# LKS32MC038Y6P8B_BP85226DF_LKSP1D5007D_V1.net
KiCad netlist of a schematic drawn in Altium Designer
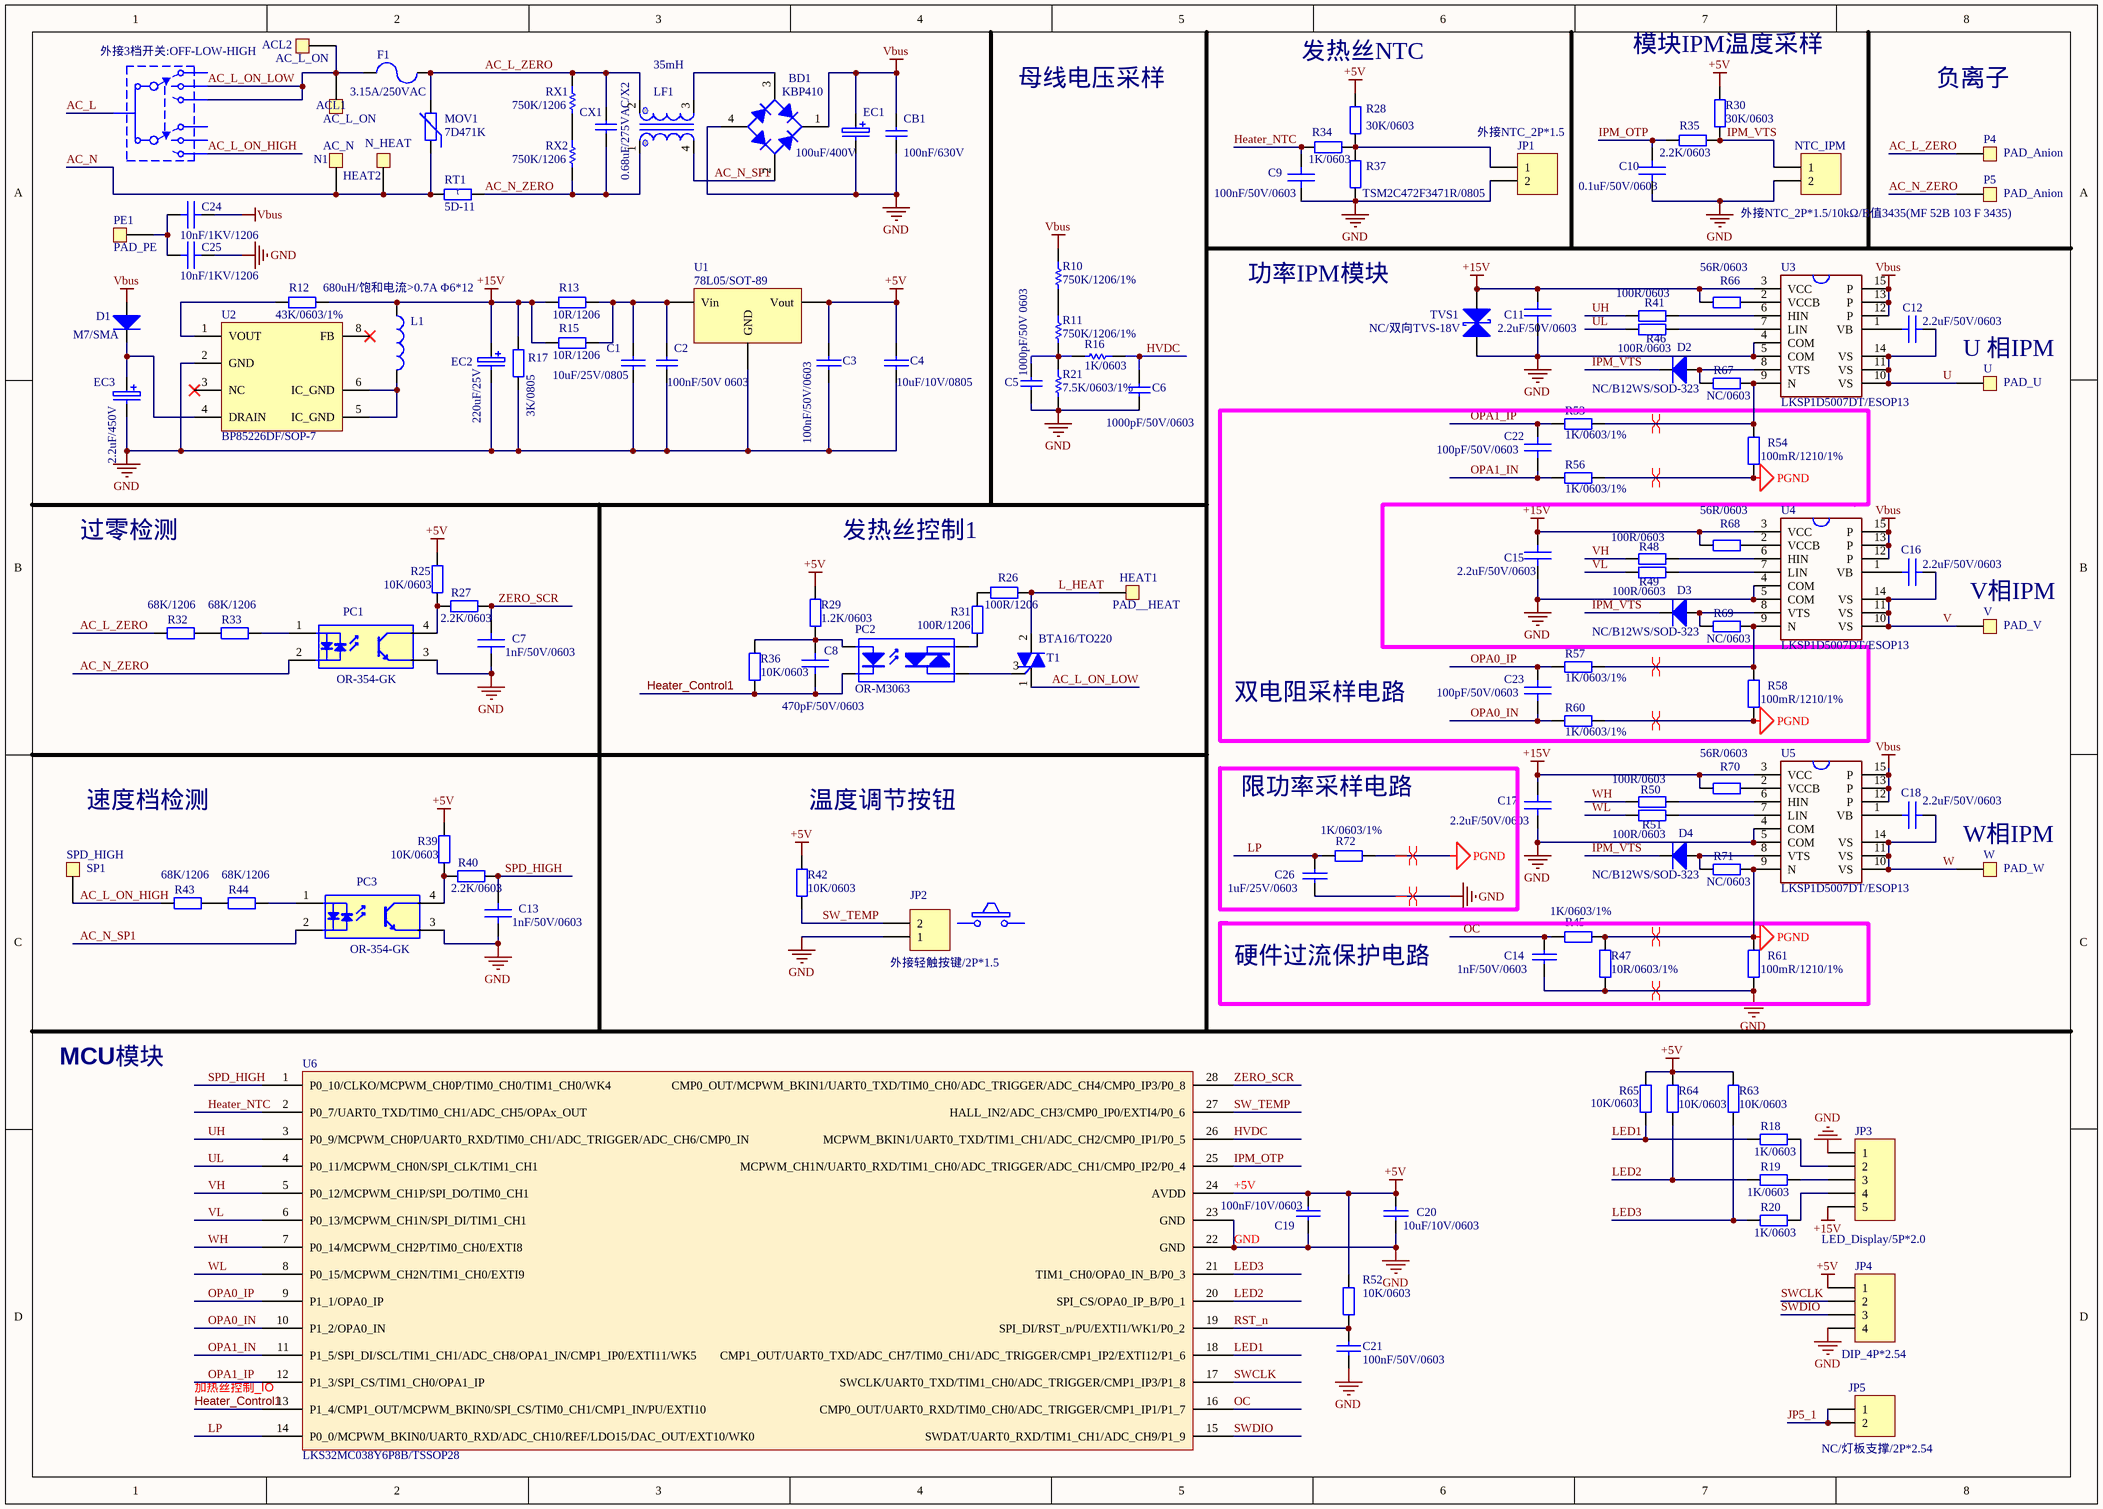
[diagram p0: LKS32MC038Y6P8B+BP85226DF+LKSP1D5007D_V1.0_SCH_20230419.SchDoc]

(export (version "E")
  (design (tool "Eeschema 10.0.6"))
  (components
    (comp (ref "ACL1") (value "AC_L_ON") (footprint "22AWG") (libsource (lib "") (part "Header-1-PE_3")))
    (comp (ref "ACL2")
      (value "AC_L_ON")
      (footprint "22AWG")
      (libsource (lib "Sch-LIB-chen") (part "Header-1-PE"))
    )
    (comp (ref "BD1") (value "KBP410") (footprint "KBP210") (libsource (lib "Sch-LIB-chen") (part "BD")))
    (comp (ref "C1")
      (value "10uF/25V/0805")
      (footprint "C0805")
      (description "Capacitor")
      (libsource (lib "*") (part "C"))
    )
    (comp (ref "C2")
      (value "100nF/50V 0603")
      (footprint "C0603")
      (libsource (lib "Sch-LIB-chen") (part "C-0603"))
    )
    (comp (ref "C3")
      (value "100nF/50V/0603")
      (footprint "C0603")
      (description "Capacitor")
      (libsource (lib "*") (part "C"))
    )
    (comp (ref "C4")
      (value "10uF/10V/0805")
      (footprint "C0805")
      (description "Capacitor")
      (libsource (lib "*") (part "C"))
    )
    (comp (ref "C5")
      (value "1000pF/50V 0603")
      (footprint "C0603")
      (libsource (lib "Sch-LIB-chen") (part "C-0603"))
    )
    (comp (ref "C6")
      (value "1000pF/50V/0603")
      (footprint "C0603")
      (libsource (lib "Sch-LIB-chen") (part "C-0603"))
    )
    (comp (ref "C7")
      (value "1nF/50V/0603")
      (footprint "C0603")
      (libsource (lib "TEK_CHIP-sch") (part "C-0603-104K50-X7R"))
    )
    (comp (ref "C8")
      (value "470pF/50V/0603")
      (footprint "C0603")
      (description "C-0603")
      (libsource (lib "TEK_CHIP-sch") (part "C-0603-471K50-X7R"))
    )
    (comp (ref "C9")
      (value "100nF/50V/0603")
      (footprint "C0603")
      (libsource (lib "TEK_CHIP-sch") (part "C-0603-104K50-X7R"))
    )
    (comp (ref "C10")
      (value "0.1uF/50V/0603")
      (footprint "C0603")
      (libsource (lib "TEK_CHIP-sch") (part "C-0603-104K50-X7R"))
    )
    (comp (ref "C11")
      (value "2.2uF/50V/0603")
      (footprint "C1206")
      (description "0805")
      (libsource (lib "TEK_CHIP-sch") (part "C-0805-475K50-X7R"))
    )
    (comp (ref "C12")
      (value "2.2uF/50V/0603")
      (footprint "C0805")
      (description "C-0805")
      (libsource (lib "SCH-Tineco") (part "C-0805-225K50-X7R"))
    )
    (comp (ref "C13")
      (value "1nF/50V/0603")
      (footprint "C0603")
      (libsource (lib "TEK_CHIP-sch") (part "C-0603-104K50-X7R"))
    )
    (comp (ref "C14")
      (value "1nF/50V/0603")
      (footprint "C0603")
      (description "Capacitor")
      (libsource (lib "*") (part "C"))
    )
    (comp (ref "C15")
      (value "2.2uF/50V/0603")
      (footprint "C1206")
      (description "0805")
      (libsource (lib "TEK_CHIP-sch") (part "C-0805-475K50-X7R"))
    )
    (comp (ref "C16")
      (value "2.2uF/50V/0603")
      (footprint "C0805")
      (description "C-0805")
      (libsource (lib "SCH-Tineco") (part "C-0805-225K50-X7R"))
    )
    (comp (ref "C17")
      (value "2.2uF/50V/0603")
      (footprint "C1206")
      (description "0805")
      (libsource (lib "TEK_CHIP-sch") (part "C-0805-475K50-X7R"))
    )
    (comp (ref "C18")
      (value "2.2uF/50V/0603")
      (footprint "C0805")
      (description "C-0805")
      (libsource (lib "SCH-Tineco") (part "C-0805-225K50-X7R"))
    )
    (comp (ref "C19")
      (value "100nF/10V/0603")
      (footprint "C0603")
      (description "Capacitor")
      (libsource (lib "*") (part "C"))
    )
    (comp (ref "C20")
      (value "10uF/10V/0603")
      (footprint "C0603")
      (description "Capacitor")
      (libsource (lib "*") (part "C"))
    )
    (comp (ref "C21")
      (value "100nF/50V/0603")
      (footprint "C0603")
      (description "Capacitor")
      (libsource (lib "*") (part "C"))
    )
    (comp (ref "C22")
      (value "100pF/50V/0603")
      (footprint "C0603")
      (description "0805")
      (libsource (lib "TEK_CHIP-sch") (part "C-0805-475K50-X7R"))
    )
    (comp (ref "C23")
      (value "100pF/50V/0603")
      (footprint "C0603")
      (description "0805")
      (libsource (lib "TEK_CHIP-sch") (part "C-0805-475K50-X7R"))
    )
    (comp (ref "C24")
      (value "10nF/1KV/1206")
      (footprint "C1206")
      (description "0805")
      (libsource (lib "TEK_CHIP-sch") (part "C-0805-475K50-X7R"))
    )
    (comp (ref "C25")
      (value "10nF/1KV/1206")
      (footprint "C1206")
      (description "0805")
      (libsource (lib "TEK_CHIP-sch") (part "C-0805-475K50-X7R"))
    )
    (comp (ref "C26")
      (value "1uF/25V/0603")
      (footprint "C0603")
      (description "Capacitor")
      (libsource (lib "*") (part "C"))
    )
    (comp (ref "CB1")
      (value "100nF/630V")
      (footprint "CY2-7.5")
      (libsource (lib "Sch-LIB-chen") (part "CBB-12*6-P10"))
    )
    (comp (ref "CX1")
      (value "0.68uF/275VAC/X2")
      (footprint "0.68uF_X2_L12.8*W7.8*H13.6")
      (libsource (lib "Sch-LIB-chen") (part "CX-18*8.5-P15"))
    )
    (comp (ref "D1")
      (value "M7/SMA")
      (footprint "SMD-(DO-214AC/SMA)(H)")
      (description "SOD-123")
      (libsource (lib "TEK_CHIP-sch") (part "D-1N4148W"))
    )
    (comp (ref "D2")
      (value "NC/B12WS/SOD-323")
      (footprint "SOD-323")
      (description "SOD-123")
      (libsource (lib "TEK_CHIP-sch") (part "D-1N4148W"))
    )
    (comp (ref "D3")
      (value "NC/B12WS/SOD-323")
      (footprint "SOD-323")
      (description "SOD-123")
      (libsource (lib "TEK_CHIP-sch") (part "D-1N4148W"))
    )
    (comp (ref "D4")
      (value "NC/B12WS/SOD-323")
      (footprint "SOD-323")
      (description "SOD-123")
      (libsource (lib "TEK_CHIP-sch") (part "D-1N4148W"))
    )
    (comp (ref "EC1") (value "100uF/400V") (footprint "E18*32W") (libsource (lib "Sch-LIB-chen") (part "CD")))
    (comp (ref "EC2") (value "220uF/25V") (footprint "E6.3*7") (libsource (lib "Sch-LIB-chen") (part "CD-8")))
    (comp (ref "EC3")
      (value "2.2uF/450V")
      (footprint "E6.3*7")
      (libsource (lib "Sch-LIB-chen") (part "CD-8"))
    )
    (comp (ref "F1")
      (value "3.15A/250VAC")
      (footprint "FUSE-6528")
      (libsource (lib "Sch-LIB-chen") (part "FUSE-3.6*10"))
    )
    (comp (ref "HEAT1") (value "PAD__HEAT") (footprint "22AWG") (libsource (lib "") (part "Header-1-PE_1")))
    (comp (ref "HEAT2") (value "N_HEAT") (footprint "22AWG") (libsource (lib "") (part "Header-1-PE_2")))
    (comp (ref "JP1")
      (value "外接NTC_2P*1.5")
      (footprint "XH25-2ADW")
      (description "Header, 2-Pin")
      (fields (field (name "PUBLISHER") "Altium Limited"))
      (libsource (lib "Miscellaneous Connectors") (part "Header 2"))
    )
    (comp (ref "JP2")
      (value "外接轻触按键/2P*1.5")
      (footprint "XH25-2ADW")
      (description "Header, 2-Pin")
      (fields (field (name "PUBLISHER") "Altium Limited"))
      (libsource (lib "") (part "Header 2_1"))
    )
    (comp (ref "JP3")
      (value "LED_Display/5P*2.0")
      (footprint "PH20-5AW")
      (description "Header, 5-Pin")
      (fields (field (name "PUBLISHER") "Altium Limited"))
      (libsource (lib "Miscellaneous Connectors") (part "Header 5"))
    )
    (comp (ref "JP4")
      (value "DIP_4P*2.54")
      (footprint "JP4_P2.54")
      (description "Header, 4-Pin")
      (fields (field (name "PUBLISHER") "Altium Limited"))
      (libsource (lib "Miscellaneous Connectors") (part "Header 4"))
    )
    (comp (ref "JP5")
      (value "NC/灯板支撑/2P*2.54")
      (footprint "HDR1X2")
      (description "Header, 2-Pin")
      (fields (field (name "PUBLISHER") "Altium Limited"))
      (libsource (lib "Miscellaneous Connectors") (part "Header 2"))
    )
    (comp (ref "L1")
      (value "680uH/饱和电流>0.7A Φ6*12")
      (footprint "L3.0")
      (libsource (lib "Sch-LIB-chen") (part "L-Φ10"))
    )
    (comp (ref "LF1") (value "35mH") (footprint "L17MM") (libsource (lib "Sch-LIB-chen") (part "L--CM")))
    (comp (ref "MOV1")
      (value "7D471K")
      (footprint "07D561")
      (description "压敏")
      (libsource (lib "Sch-LIB-chen") (part "RV-10D"))
    )
    (comp (ref "N1") (value "AC_N") (footprint "22AWG") (libsource (lib "") (part "Header-1-PE_2")))
    (comp (ref "NTC_IPM")
      (value "外接NTC_2P*1.5/10kΩ/B值3435(MF 52B 103 F 3435)")
      (footprint "HDR1X2")
      (description "Header, 2-Pin")
      (fields (field (name "PUBLISHER") "Altium Limited"))
      (libsource (lib "Miscellaneous Connectors") (part "Header 2"))
    )
    (comp (ref "P4") (value "PAD_Anion") (footprint "22AWG") (libsource (lib "") (part "Header-1-PE_1")))
    (comp (ref "P5") (value "PAD_Anion") (footprint "22AWG") (libsource (lib "") (part "Header-1-PE_1")))
    (comp (ref "PC1") (value "OR-354-GK") (footprint "CTM3053+EL3H4-G") (libsource (lib "*") (part "EL3H4")))
    (comp (ref "PC2")
      (value "OR-M3063")
      (footprint "CTM3053")
      (description "SOP-4")
      (libsource (lib "SCH-Tineco") (part "PC-TLP265J"))
    )
    (comp (ref "PC3") (value "OR-354-GK") (footprint "CTM3053+EL3H4-G") (libsource (lib "*") (part "EL3H4")))
    (comp (ref "PE1")
      (value "PAD_PE")
      (footprint "22AWG")
      (libsource (lib "Sch-LIB-chen") (part "Header-1-PE"))
    )
    (comp (ref "R10")
      (value "750K/1206/1%")
      (footprint "R1206")
      (libsource (lib "Sch-LIB-chen") (part "R-1206"))
    )
    (comp (ref "R11")
      (value "750K/1206/1%")
      (footprint "R1206")
      (libsource (lib "Sch-LIB-chen") (part "R-1206"))
    )
    (comp (ref "R12")
      (value "43K/0603/1%")
      (footprint "R0603")
      (description "Resistor")
      (fields (field (name "PUBLISHER") "Altium Limited"))
      (libsource (lib "") (part "Res2_1"))
    )
    (comp (ref "R13")
      (value "10R/1206")
      (footprint "R1206")
      (description "Resistor")
      (fields (field (name "PUBLISHER") "Altium Limited"))
      (libsource (lib "") (part "Res2_1"))
    )
    (comp (ref "R15")
      (value "10R/1206")
      (footprint "R1206")
      (description "Resistor")
      (fields (field (name "PUBLISHER") "Altium Limited"))
      (libsource (lib "") (part "Res2_1"))
    )
    (comp (ref "R16") (value "1K/0603") (footprint "R0603") (libsource (lib "Sch-LIB-chen") (part "R-0603")))
    (comp (ref "R17")
      (value "3K/0805")
      (footprint "R0805")
      (description "0805 resistor")
      (libsource (lib "TEK_CHIP-sch") (part "R-0805-0R--J"))
    )
    (comp (ref "R18")
      (value "1K/0603")
      (footprint "R0603")
      (description "R-1206")
      (libsource (lib "TEK_CHIP-sch") (part "R-1206-200K-F"))
    )
    (comp (ref "R19")
      (value "1K/0603")
      (footprint "R0603")
      (description "R-1206")
      (libsource (lib "TEK_CHIP-sch") (part "R-1206-200K-F"))
    )
    (comp (ref "R20")
      (value "1K/0603")
      (footprint "R0603")
      (description "R-1206")
      (libsource (lib "TEK_CHIP-sch") (part "R-1206-200K-F"))
    )
    (comp (ref "R21")
      (value "7.5K/0603/1%")
      (footprint "R0603")
      (libsource (lib "Sch-LIB-chen") (part "R-1206"))
    )
    (comp (ref "R25")
      (value "10K/0603")
      (footprint "R0603")
      (description "Resistor")
      (fields (field (name "PUBLISHER") "Altium Limited"))
      (libsource (lib "") (part "Res2_1"))
    )
    (comp (ref "R26")
      (value "100R/1206")
      (footprint "R1206")
      (description "1206 resistor")
      (libsource (lib "") (part "R-1206-270--F_1"))
    )
    (comp (ref "R27")
      (value "2.2K/0603")
      (footprint "R0603")
      (description "R-0603")
      (libsource (lib "TEK_CHIP-sch") (part "R-0603-2.2K-F"))
    )
    (comp (ref "R28")
      (value "30K/0603")
      (footprint "R0603")
      (description "0603 resistor")
      (libsource (lib "") (part "R-0603-10K-J_1"))
    )
    (comp (ref "R29")
      (value "1.2K/0603")
      (footprint "R0603")
      (description "0603 resistor")
      (libsource (lib "TEK_CHIP-sch") (part "R-0603-100--J"))
    )
    (comp (ref "R30")
      (value "30K/0603")
      (footprint "R0603")
      (description "0603 resistor")
      (libsource (lib "TEK_CHIP-sch") (part "R-0603-5.1K-F"))
    )
    (comp (ref "R31")
      (value "100R/1206")
      (footprint "R1206")
      (description "1206 resistor")
      (libsource (lib "TEK_CHIP-sch") (part "R-1206-270--F"))
    )
    (comp (ref "R32")
      (value "68K/1206")
      (footprint "R1206")
      (description "Resistor")
      (fields (field (name "PUBLISHER") "Altium Limited"))
      (libsource (lib "*") (part "Res2"))
    )
    (comp (ref "R33")
      (value "68K/1206")
      (footprint "R1206")
      (description "Resistor")
      (fields (field (name "PUBLISHER") "Altium Limited"))
      (libsource (lib "*") (part "Res2"))
    )
    (comp (ref "R34")
      (value "1K/0603")
      (footprint "R0603")
      (description "0603 resistor")
      (libsource (lib "TEK_CHIP-sch") (part "R-0603-10K-J"))
    )
    (comp (ref "R35")
      (value "2.2K/0603")
      (footprint "R0603")
      (description "0603 resistor")
      (libsource (lib "") (part "R-0603-5.1K-F_1"))
    )
    (comp (ref "R36")
      (value "10K/0603")
      (footprint "R0603")
      (description "0603 resistor")
      (libsource (lib "TEK_CHIP-sch") (part "R-0603-100--J"))
    )
    (comp (ref "R37")
      (value "TSM2C472F3471R/0805")
      (footprint "R0805")
      (description "0805 resistor")
      (libsource (lib "TEK_CHIP-sch") (part "R-0805-0R--J"))
    )
    (comp (ref "R39")
      (value "10K/0603")
      (footprint "R0603")
      (description "Resistor")
      (fields (field (name "PUBLISHER") "Altium Limited"))
      (libsource (lib "") (part "Res2_1"))
    )
    (comp (ref "R40")
      (value "2.2K/0603")
      (footprint "R0603")
      (description "R-0603")
      (libsource (lib "TEK_CHIP-sch") (part "R-0603-2.2K-F"))
    )
    (comp (ref "R41")
      (value "100R/0603")
      (footprint "R0603")
      (description "R-0805")
      (libsource (lib "SCH-Tineco") (part "R-0805-3.6K--F"))
    )
    (comp (ref "R42")
      (value "10K/0603")
      (footprint "R0603")
      (description "Resistor")
      (fields (field (name "PUBLISHER") "Altium Limited"))
      (libsource (lib "") (part "Res2_2"))
    )
    (comp (ref "R43")
      (value "68K/1206")
      (footprint "R1206")
      (description "Resistor")
      (fields (field (name "PUBLISHER") "Altium Limited"))
      (libsource (lib "*") (part "Res2"))
    )
    (comp (ref "R44")
      (value "68K/1206")
      (footprint "R1206")
      (description "Resistor")
      (fields (field (name "PUBLISHER") "Altium Limited"))
      (libsource (lib "*") (part "Res2"))
    )
    (comp (ref "R45")
      (value "1K/0603/1%")
      (footprint "R0603")
      (description "Resistor")
      (fields (field (name "PUBLISHER") "Altium Limited"))
      (libsource (lib "") (part "Res2_1"))
    )
    (comp (ref "R46")
      (value "100R/0603")
      (footprint "R0603")
      (description "R-0805")
      (libsource (lib "SCH-Tineco") (part "R-0805-3.6K--F"))
    )
    (comp (ref "R47")
      (value "10R/0603/1%")
      (footprint "R0603")
      (description "R-1206")
      (libsource (lib "SCH-Tineco") (part "R-1206-10R-F"))
    )
    (comp (ref "R48")
      (value "100R/0603")
      (footprint "R0603")
      (description "R-0805")
      (libsource (lib "SCH-Tineco") (part "R-0805-3.6K--F"))
    )
    (comp (ref "R49")
      (value "100R/0603")
      (footprint "R0603")
      (description "R-0805")
      (libsource (lib "SCH-Tineco") (part "R-0805-3.6K--F"))
    )
    (comp (ref "R50")
      (value "100R/0603")
      (footprint "R0603")
      (description "R-0805")
      (libsource (lib "SCH-Tineco") (part "R-0805-3.6K--F"))
    )
    (comp (ref "R51")
      (value "100R/0603")
      (footprint "R0603")
      (description "R-0805")
      (libsource (lib "SCH-Tineco") (part "R-0805-3.6K--F"))
    )
    (comp (ref "R52")
      (value "10K/0603")
      (footprint "R0603")
      (description "Resistor")
      (fields (field (name "PUBLISHER") "Altium Limited"))
      (libsource (lib "Miscellaneous Devices") (part "Res2"))
    )
    (comp (ref "R53")
      (value "1K/0603/1%")
      (footprint "R0603")
      (description "Resistor")
      (fields (field (name "Comment") "1K 1%") (field (name "PUBLISHER") "Altium Limited"))
      (libsource (lib "Miscellaneous Devices") (part "Res2"))
    )
    (comp (ref "R54")
      (value "100mR/1210/1%")
      (footprint "R1206")
      (description "R-1206")
      (libsource (lib "SCH-Tineco") (part "R-1206-1R-F"))
    )
    (comp (ref "R56")
      (value "1K/0603/1%")
      (footprint "R0603")
      (description "Resistor")
      (fields (field (name "Comment") "1K 1%") (field (name "PUBLISHER") "Altium Limited"))
      (libsource (lib "Miscellaneous Devices") (part "Res2"))
    )
    (comp (ref "R57")
      (value "1K/0603/1%")
      (footprint "R0603")
      (description "Resistor")
      (fields (field (name "Comment") "1K 1%") (field (name "PUBLISHER") "Altium Limited"))
      (libsource (lib "Miscellaneous Devices") (part "Res2"))
    )
    (comp (ref "R58")
      (value "100mR/1210/1%")
      (footprint "R1206")
      (description "R-1206")
      (libsource (lib "SCH-Tineco") (part "R-1206-1R-F"))
    )
    (comp (ref "R60")
      (value "1K/0603/1%")
      (footprint "R0603")
      (description "Resistor")
      (fields (field (name "Comment") "1K 1%") (field (name "PUBLISHER") "Altium Limited"))
      (libsource (lib "Miscellaneous Devices") (part "Res2"))
    )
    (comp (ref "R61")
      (value "100mR/1210/1%")
      (footprint "R1206")
      (description "R-1206")
      (libsource (lib "SCH-Tineco") (part "R-1206-1R-F"))
    )
    (comp (ref "R63")
      (value "10K/0603")
      (footprint "R0603")
      (description "Resistor")
      (fields (field (name "PUBLISHER") "Altium Limited"))
      (libsource (lib "Miscellaneous Devices") (part "Res2"))
    )
    (comp (ref "R64")
      (value "10K/0603")
      (footprint "R0603")
      (description "Resistor")
      (fields (field (name "PUBLISHER") "Altium Limited"))
      (libsource (lib "Miscellaneous Devices") (part "Res2"))
    )
    (comp (ref "R65")
      (value "10K/0603")
      (footprint "R0603")
      (description "Resistor")
      (fields (field (name "PUBLISHER") "Altium Limited"))
      (libsource (lib "Miscellaneous Devices") (part "Res2"))
    )
    (comp (ref "R66")
      (value "56R/0603")
      (footprint "R0603")
      (description "R-0805")
      (libsource (lib "SCH-Tineco") (part "R-0805-3.6K--F"))
    )
    (comp (ref "R67")
      (value "NC/0603")
      (footprint "R0603")
      (description "R-0805")
      (libsource (lib "") (part "R-0805-3.6K--F_1"))
    )
    (comp (ref "R68")
      (value "56R/0603")
      (footprint "R0603")
      (description "R-0805")
      (libsource (lib "SCH-Tineco") (part "R-0805-3.6K--F"))
    )
    (comp (ref "R69")
      (value "NC/0603")
      (footprint "R0603")
      (description "R-0805")
      (libsource (lib "") (part "R-0805-3.6K--F_1"))
    )
    (comp (ref "R70")
      (value "56R/0603")
      (footprint "R0603")
      (description "R-0805")
      (libsource (lib "SCH-Tineco") (part "R-0805-3.6K--F"))
    )
    (comp (ref "R71")
      (value "NC/0603")
      (footprint "R0603")
      (description "R-0805")
      (libsource (lib "") (part "R-0805-3.6K--F_1"))
    )
    (comp (ref "R72")
      (value "1K/0603/1%")
      (footprint "R0603")
      (description "Resistor")
      (fields (field (name "PUBLISHER") "Altium Limited"))
      (libsource (lib "") (part "Res2_1"))
    )
    (comp (ref "RT1")
      (value "5D-11")
      (footprint "07D561")
      (description "热敏")
      (libsource (lib "Sch-LIB-chen") (part "RT-10D"))
    )
    (comp (ref "RX1")
      (value "750K/1206")
      (footprint "R1206")
      (libsource (lib "Sch-LIB-chen") (part "R-1206"))
    )
    (comp (ref "RX2")
      (value "750K/1206")
      (footprint "R1206")
      (libsource (lib "Sch-LIB-chen") (part "R-1206"))
    )
    (comp (ref "SP1") (value "SPD_HIGH") (footprint "22AWG") (libsource (lib "") (part "Header-1-PE_2")))
    (comp (ref "T1")
      (value "BTA16/TO220")
      (footprint "TO-220-2A")
      (description "TO-220")
      (libsource (lib "SCH-Tineco") (part "T-BTA16"))
    )
    (comp (ref "TVS1")
      (value "NC/双向TVS-18V")
      (footprint "SMD-(DO-214AC/SMA)(H)")
      (description "ESD-0603")
      (libsource (lib "SCH-Tineco") (part "ESD-ESDA0603 -LC"))
    )
    (comp (ref "U") (value "PAD_U") (footprint "22AWG") (libsource (lib "") (part "Header-1-PE_1")))
    (comp (ref "U1")
      (value "78L05/SOT-89")
      (footprint "BP_PCB_Lib:SOT-89")
      (libsource (lib "*") (part "VOL-78"))
    )
    (comp (ref "U2")
      (value "BP85226DF/SOP-7")
      (footprint "SO-8")
      (libsource (lib "LKS038风筒参考原理图-修改037-3") (part "BP85256D"))
    )
    (comp (ref "U3")
      (value "LKSP1D5007DT/ESOP13")
      (footprint "LKSP1D5007D-ESOP13")
      (description "Gate Driver")
      (libsource (lib "LKS32MC038Y6P8B+BP85226DF+BP1D5007D_V1.0_Project") (part "BP1N4005D"))
    )
    (comp (ref "U4")
      (value "LKSP1D5007DT/ESOP13")
      (footprint "LKSP1D5007D-ESOP13")
      (description "Gate Driver")
      (libsource (lib "LKS32MC038Y6P8B+BP85226DF+BP1D5007D_V1.0_Project") (part "BP1N4005D"))
    )
    (comp (ref "U5")
      (value "LKSP1D5007DT/ESOP13")
      (footprint "LKSP1D5007D-ESOP13")
      (description "Gate Driver")
      (libsource (lib "LKS32MC038Y6P8B+BP85226DF+BP1D5007D_V1.0_Project") (part "BP1N4005D"))
    )
    (comp (ref "U6")
      (value "LKS32MC038Y6P8B/TSSOP28")
      (footprint "TSSOP28")
      (description "TSSOP28")
      (libsource (lib "LKS32MC037M6S8+BP1D5007QA_V1.0_Project") (part "LKS32MC038Y6P8B"))
    )
    (comp (ref "V") (value "PAD_V") (footprint "22AWG") (libsource (lib "") (part "Header-1-PE_1")))
    (comp (ref "W") (value "PAD_W") (footprint "22AWG") (libsource (lib "") (part "Header-1-PE_1")))
  )
  (nets
    (net (code "1") (name "+5V") (class "Default")
      (node (ref "C19") (pin "2") (pinfunction "2_2") (pintype "passive"))
      (node (ref "C20") (pin "2") (pinfunction "2_2") (pintype "passive"))
      (node (ref "C3") (pin "2") (pinfunction "2_2") (pintype "passive"))
      (node (ref "C4") (pin "2") (pinfunction "2_2") (pintype "passive"))
      (node (ref "JP4") (pin "1") (pinfunction "1_1") (pintype "passive"))
      (node (ref "R25") (pin "2") (pinfunction "2_2") (pintype "passive"))
      (node (ref "R28") (pin "2") (pinfunction "2_2") (pintype "passive"))
      (node (ref "R29") (pin "2") (pinfunction "2_2") (pintype "passive"))
      (node (ref "R30") (pin "1") (pinfunction "1_1") (pintype "passive"))
      (node (ref "R39") (pin "2") (pinfunction "2_2") (pintype "passive"))
      (node (ref "R42") (pin "1") (pinfunction "1_1") (pintype "passive"))
      (node (ref "R52") (pin "1") (pinfunction "1_1") (pintype "passive"))
      (node (ref "R63") (pin "1") (pinfunction "1_1") (pintype "passive"))
      (node (ref "R64") (pin "1") (pinfunction "1_1") (pintype "passive"))
      (node (ref "R65") (pin "1") (pinfunction "1_1") (pintype "passive"))
      (node (ref "U1") (pin "1") (pinfunction "Vout_1") (pintype "passive"))
      (node (ref "U6") (pin "24") (pinfunction "AVDD_24") (pintype "passive"))
    )
    (net (code "2") (name "+15V") (class "Default")
      (node (ref "C11") (pin "1") (pinfunction "1_1") (pintype "passive"))
      (node (ref "C15") (pin "1") (pinfunction "1_1") (pintype "passive"))
      (node (ref "C17") (pin "1") (pinfunction "1_1") (pintype "passive"))
      (node (ref "EC2") (pin "1") (pinfunction "+_1") (pintype "passive"))
      (node (ref "JP3") (pin "5") (pinfunction "5_5") (pintype "passive"))
      (node (ref "L1") (pin "1") (pinfunction "1_1") (pintype "passive"))
      (node (ref "R12") (pin "1") (pinfunction "1_1") (pintype "passive"))
      (node (ref "R13") (pin "2") (pinfunction "2_2") (pintype "passive"))
      (node (ref "R15") (pin "2") (pinfunction "2_2") (pintype "passive"))
      (node (ref "R17") (pin "1") (pinfunction "1_1") (pintype "passive"))
      (node (ref "R66") (pin "1") (pinfunction "1_1") (pintype "passive"))
      (node (ref "R68") (pin "1") (pinfunction "1_1") (pintype "passive"))
      (node (ref "R70") (pin "1") (pinfunction "1_1") (pintype "passive"))
      (node (ref "TVS1") (pin "2") (pinfunction "K_2") (pintype "passive"))
      (node (ref "U3") (pin "3") (pinfunction "VCC_3") (pintype "passive"))
      (node (ref "U4") (pin "3") (pinfunction "VCC_3") (pintype "passive"))
      (node (ref "U5") (pin "3") (pinfunction "VCC_3") (pintype "passive"))
    )
    (net (code "4") (name "/AC_L_ON_HIGH") (class "Default")
      (node (ref "R43") (pin "1") (pinfunction "1_1") (pintype "passive"))
      (node (ref "SP1") (pin "1") (pintype "passive"))
    )
    (net (code "5") (name "/AC_L_ON_LOW") (class "Default")
      (node (ref "ACL1") (pin "1") (pintype "passive"))
      (node (ref "ACL2") (pin "1") (pintype "passive"))
      (node (ref "F1") (pin "1") (pinfunction "1_1") (pintype "passive"))
      (node (ref "T1") (pin "1") (pinfunction "1_1") (pintype "passive"))
    )
    (net (code "6") (name "/AC_L_ZERO") (class "Default")
      (node (ref "CX1") (pin "2") (pintype "passive"))
      (node (ref "F1") (pin "2") (pinfunction "2_2") (pintype "passive"))
      (node (ref "LF1") (pin "2") (pinfunction "2_2") (pintype "passive"))
      (node (ref "MOV1") (pin "2") (pinfunction "2_2") (pintype "passive"))
      (node (ref "P4") (pin "1") (pintype "passive"))
      (node (ref "R32") (pin "1") (pinfunction "1_1") (pintype "passive"))
      (node (ref "RX1") (pin "2") (pinfunction "2_2") (pintype "passive"))
    )
    (net (code "7") (name "/AC_N") (class "Default")
      (node (ref "HEAT2") (pin "1") (pintype "passive"))
      (node (ref "MOV1") (pin "1") (pinfunction "1_1") (pintype "passive"))
      (node (ref "N1") (pin "1") (pintype "passive"))
      (node (ref "RT1") (pin "1") (pinfunction "1_1") (pintype "passive"))
    )
    (net (code "8") (name "/AC_N_SP1") (class "Default")
      (node (ref "BD1") (pin "2") (pinfunction "C_2") (pintype "passive"))
      (node (ref "LF1") (pin "4") (pinfunction "4_4") (pintype "passive"))
      (node (ref "PC3") (pin "2") (pinfunction "2_2") (pintype "passive"))
    )
    (net (code "9") (name "/AC_N_ZERO") (class "Default")
      (node (ref "CX1") (pin "1") (pintype "passive"))
      (node (ref "LF1") (pin "1") (pinfunction "1_1") (pintype "passive"))
      (node (ref "P5") (pin "1") (pintype "passive"))
      (node (ref "PC1") (pin "2") (pinfunction "2_2") (pintype "passive"))
      (node (ref "RT1") (pin "2") (pinfunction "2_2") (pintype "passive"))
      (node (ref "RX2") (pin "1") (pinfunction "1_1") (pintype "passive"))
    )
    (net (code "10") (name "/HVDC") (class "Default")
      (node (ref "C6") (pin "2") (pintype "passive"))
      (node (ref "R16") (pin "2") (pinfunction "2_2") (pintype "passive"))
      (node (ref "U6") (pin "26") (pinfunction "MCPWM_BKIN1/UART0_TXD/TIM1_CH1/ADC_CH2/CMP0_IP1/P0_5_26") (pintype "passive"))
    )
    (net (code "11") (name "/Heater_Control1") (class "Default")
      (node (ref "C8") (pin "2") (pinfunction "2_2") (pintype "passive"))
      (node (ref "PC2") (pin "2") (pinfunction "K_2") (pintype "passive"))
      (node (ref "R36") (pin "1") (pinfunction "1_1") (pintype "passive"))
      (node (ref "U6") (pin "13") (pinfunction "P1_4/CMP1_OUT/MCPWM_BKIN0/SPI_CS/TIM0_CH1/CMP1_IN/PU/EXTI10_13") (pintype "passive"))
    )
    (net (code "12") (name "/Heater_NTC") (class "Default")
      (node (ref "C9") (pin "2") (pinfunction "2_2") (pintype "passive"))
      (node (ref "R34") (pin "2") (pinfunction "2_2") (pintype "passive"))
      (node (ref "U6") (pin "2") (pinfunction "P0_7/UART0_TXD/TIM0_CH1/ADC_CH5/OPAx_OUT_2") (pintype "passive"))
    )
    (net (code "13") (name "/IPM_OTP") (class "Default")
      (node (ref "C10") (pin "2") (pinfunction "2_2") (pintype "passive"))
      (node (ref "R35") (pin "2") (pinfunction "2_2") (pintype "passive"))
      (node (ref "U6") (pin "25") (pinfunction "MCPWM_CH1N/UART0_RXD/TIM1_CH0/ADC_TRIGGER/ADC_CH1/CMP0_IP2/P0_4_25") (pintype "passive"))
    )
    (net (code "14") (name "/IPM_VTS") (class "Default")
      (node (ref "D2") (pin "2") (pinfunction "2_2") (pintype "passive"))
      (node (ref "D3") (pin "2") (pinfunction "2_2") (pintype "passive"))
      (node (ref "D4") (pin "2") (pinfunction "2_2") (pintype "passive"))
      (node (ref "NTC_IPM") (pin "1") (pinfunction "1_1") (pintype "passive"))
      (node (ref "R30") (pin "2") (pinfunction "2_2") (pintype "passive"))
      (node (ref "R35") (pin "1") (pinfunction "1_1") (pintype "passive"))
    )
    (net (code "15") (name "/JP5_1") (class "Default")
      (node (ref "JP5") (pin "1") (pinfunction "1_1") (pintype "passive"))
      (node (ref "JP5") (pin "2") (pinfunction "2_2") (pintype "passive"))
    )
    (net (code "16") (name "/LED1") (class "Default")
      (node (ref "R18") (pin "2") (pinfunction "2_2") (pintype "passive"))
      (node (ref "R65") (pin "2") (pinfunction "2_2") (pintype "passive"))
      (node (ref "U6") (pin "18") (pinfunction "CMP1_OUT/UART0_TXD/ADC_CH7/TIM0_CH1/ADC_TRIGGER/CMP1_IP2/EXTI12/P1_6_18") (pintype "passive"))
    )
    (net (code "17") (name "/LED2") (class "Default")
      (node (ref "R19") (pin "2") (pinfunction "2_2") (pintype "passive"))
      (node (ref "R64") (pin "2") (pinfunction "2_2") (pintype "passive"))
      (node (ref "U6") (pin "20") (pinfunction "SPI_CS/OPA0_IP_B/P0_1_20") (pintype "passive"))
    )
    (net (code "18") (name "/LED3") (class "Default")
      (node (ref "R20") (pin "2") (pinfunction "2_2") (pintype "passive"))
      (node (ref "R63") (pin "2") (pinfunction "2_2") (pintype "passive"))
      (node (ref "U6") (pin "21") (pinfunction "TIM1_CH0/OPA0_IN_B/P0_3_21") (pintype "passive"))
    )
    (net (code "19") (name "/LP") (class "Default")
      (node (ref "C26") (pin "2") (pinfunction "2_2") (pintype "passive"))
      (node (ref "R72") (pin "2") (pinfunction "2_2") (pintype "passive"))
      (node (ref "U6") (pin "14") (pinfunction "P0_0/MCPWM_BKIN0/UART0_RXD/ADC_CH10/REF/LDO15/DAC_OUT/EXT10/WK0_14") (pintype "passive"))
    )
    (net (code "20") (name "/L_HEAT") (class "Default")
      (node (ref "HEAT1") (pin "1") (pintype "passive"))
      (node (ref "R26") (pin "2") (pinfunction "2_2") (pintype "passive"))
      (node (ref "T1") (pin "2") (pinfunction "2_2") (pintype "passive"))
    )
    (net (code "21") (name "/OC") (class "Default")
      (node (ref "C14") (pin "2") (pinfunction "2_2") (pintype "passive"))
      (node (ref "R45") (pin "2") (pinfunction "2_2") (pintype "passive"))
      (node (ref "U6") (pin "16") (pinfunction "CMP0_OUT/UART0_RXD/TIM0_CH0/ADC_TRIGGER/CMP1_IP1/P1_7_16") (pintype "passive"))
    )
    (net (code "22") (name "/OPA0_IN") (class "Default")
      (node (ref "C23") (pin "2") (pinfunction "2_2") (pintype "passive"))
      (node (ref "R60") (pin "2") (pinfunction "2_2") (pintype "passive"))
      (node (ref "U6") (pin "10") (pinfunction "P1_2/OPA0_IN_10") (pintype "passive"))
    )
    (net (code "23") (name "/OPA0_IP") (class "Default")
      (node (ref "C23") (pin "1") (pinfunction "1_1") (pintype "passive"))
      (node (ref "R57") (pin "2") (pinfunction "2_2") (pintype "passive"))
      (node (ref "U6") (pin "9") (pinfunction "P1_1/OPA0_IP_9") (pintype "passive"))
    )
    (net (code "24") (name "/OPA1_IN") (class "Default")
      (node (ref "C22") (pin "2") (pinfunction "2_2") (pintype "passive"))
      (node (ref "R56") (pin "2") (pinfunction "2_2") (pintype "passive"))
      (node (ref "U6") (pin "11") (pinfunction "P1_5/SPI_DI/SCL/TIM1_CH1/ADC_CH8/OPA1_IN/CMP1_IP0/EXTI11/WK5_11") (pintype "passive"))
    )
    (net (code "25") (name "/OPA1_IP") (class "Default")
      (node (ref "C22") (pin "1") (pinfunction "1_1") (pintype "passive"))
      (node (ref "R53") (pin "2") (pinfunction "2_2") (pintype "passive"))
      (node (ref "U6") (pin "12") (pinfunction "P1_3/SPI_CS/TIM1_CH0/OPA1_IP_12") (pintype "passive"))
    )
    (net (code "26") (name "/RST_n") (class "Default")
      (node (ref "C21") (pin "1") (pinfunction "1_1") (pintype "passive"))
      (node (ref "R52") (pin "2") (pinfunction "2_2") (pintype "passive"))
      (node (ref "U6") (pin "19") (pinfunction "SPI_DI/RST_n/PU/EXTI1/WK1/P0_2_19") (pintype "passive"))
    )
    (net (code "27") (name "/SPD_HIGH") (class "Default")
      (node (ref "C13") (pin "2") (pinfunction "2_2") (pintype "passive"))
      (node (ref "R40") (pin "2") (pinfunction "2_2") (pintype "passive"))
      (node (ref "U6") (pin "1") (pinfunction "P0_10/CLKO/MCPWM_CH0P/TIM0_CH0/TIM1_CH0/WK4_1") (pintype "passive"))
    )
    (net (code "28") (name "/SWCLK") (class "Default")
      (node (ref "JP4") (pin "2") (pinfunction "2_2") (pintype "passive"))
      (node (ref "U6") (pin "17") (pinfunction "SWCLK/UART0_TXD/TIM1_CH0/ADC_TRIGGER/CMP1_IP3/P1_8_17") (pintype "passive"))
    )
    (net (code "29") (name "/SWDIO") (class "Default")
      (node (ref "JP4") (pin "3") (pinfunction "3_3") (pintype "passive"))
      (node (ref "U6") (pin "15") (pinfunction "SWDAT/UART0_RXD/TIM1_CH1/ADC_CH9/P1_9_15") (pintype "passive"))
    )
    (net (code "30") (name "/SW_TEMP") (class "Default")
      (node (ref "JP2") (pin "2") (pinfunction "2_2") (pintype "passive"))
      (node (ref "R42") (pin "2") (pinfunction "2_2") (pintype "passive"))
      (node (ref "U6") (pin "27") (pinfunction "HALL_IN2/ADC_CH3/CMP0_IP0/EXTI4/P0_6_27") (pintype "passive"))
    )
    (net (code "31") (name "/U") (class "Default")
      (node (ref "C12") (pin "2") (pinfunction "2_2") (pintype "passive"))
      (node (ref "U") (pin "1") (pintype "passive"))
      (node (ref "U3") (pin "10") (pinfunction "VS_10") (pintype "passive"))
      (node (ref "U3") (pin "11") (pinfunction "VS_11") (pintype "passive"))
      (node (ref "U3") (pin "14") (pinfunction "VS_14") (pintype "passive"))
    )
    (net (code "32") (name "/UH") (class "Default")
      (node (ref "R41") (pin "1") (pinfunction "1_1") (pintype "passive"))
      (node (ref "U6") (pin "3") (pinfunction "P0_9/MCPWM_CH0P/UART0_RXD/TIM0_CH1/ADC_TRIGGER/ADC_CH6/CMP0_IN_3") (pintype "passive"))
    )
    (net (code "33") (name "/UL") (class "Default")
      (node (ref "R46") (pin "1") (pinfunction "1_1") (pintype "passive"))
      (node (ref "U6") (pin "4") (pinfunction "P0_11/MCPWM_CH0N/SPI_CLK/TIM1_CH1_4") (pintype "passive"))
    )
    (net (code "34") (name "/V") (class "Default")
      (node (ref "C16") (pin "2") (pinfunction "2_2") (pintype "passive"))
      (node (ref "U4") (pin "10") (pinfunction "VS_10") (pintype "passive"))
      (node (ref "U4") (pin "11") (pinfunction "VS_11") (pintype "passive"))
      (node (ref "U4") (pin "14") (pinfunction "VS_14") (pintype "passive"))
      (node (ref "V") (pin "1") (pintype "passive"))
    )
    (net (code "35") (name "/VH") (class "Default")
      (node (ref "R48") (pin "1") (pinfunction "1_1") (pintype "passive"))
      (node (ref "U6") (pin "5") (pinfunction "P0_12/MCPWM_CH1P/SPI_DO/TIM0_CH1_5") (pintype "passive"))
    )
    (net (code "36") (name "/VL") (class "Default")
      (node (ref "R49") (pin "1") (pinfunction "1_1") (pintype "passive"))
      (node (ref "U6") (pin "6") (pinfunction "P0_13/MCPWM_CH1N/SPI_DI/TIM1_CH1_6") (pintype "passive"))
    )
    (net (code "37") (name "/W") (class "Default")
      (node (ref "C18") (pin "2") (pinfunction "2_2") (pintype "passive"))
      (node (ref "U5") (pin "10") (pinfunction "VS_10") (pintype "passive"))
      (node (ref "U5") (pin "11") (pinfunction "VS_11") (pintype "passive"))
      (node (ref "U5") (pin "14") (pinfunction "VS_14") (pintype "passive"))
      (node (ref "W") (pin "1") (pintype "passive"))
    )
    (net (code "38") (name "/WH") (class "Default")
      (node (ref "R50") (pin "1") (pinfunction "1_1") (pintype "passive"))
      (node (ref "U6") (pin "7") (pinfunction "P0_14/MCPWM_CH2P/TIM0_CH0/EXTI8_7") (pintype "passive"))
    )
    (net (code "39") (name "/WL") (class "Default")
      (node (ref "R51") (pin "1") (pinfunction "1_1") (pintype "passive"))
      (node (ref "U6") (pin "8") (pinfunction "P0_15/MCPWM_CH2N/TIM1_CH0/EXTI9_8") (pintype "passive"))
    )
    (net (code "40") (name "/ZERO_SCR") (class "Default")
      (node (ref "C7") (pin "2") (pinfunction "2_2") (pintype "passive"))
      (node (ref "R27") (pin "2") (pinfunction "2_2") (pintype "passive"))
      (node (ref "U6") (pin "28") (pinfunction "CMP0_OUT/MCPWM_BKIN1/UART0_TXD/TIM0_CH0/ADC_TRIGGER/ADC_CH4/CMP0_IP3/P0_8_28") (pintype "passive"))
    )
    (net (code "42") (name "GND") (class "Default")
      (node (ref "BD1") (pin "4") (pinfunction "A_4") (pintype "passive"))
      (node (ref "C1") (pin "1") (pinfunction "1_1") (pintype "passive"))
      (node (ref "C10") (pin "1") (pinfunction "1_1") (pintype "passive"))
      (node (ref "C11") (pin "2") (pinfunction "2_2") (pintype "passive"))
      (node (ref "C13") (pin "1") (pinfunction "1_1") (pintype "passive"))
      (node (ref "C14") (pin "1") (pinfunction "1_1") (pintype "passive"))
      (node (ref "C15") (pin "2") (pinfunction "2_2") (pintype "passive"))
      (node (ref "C17") (pin "2") (pinfunction "2_2") (pintype "passive"))
      (node (ref "C19") (pin "1") (pinfunction "1_1") (pintype "passive"))
      (node (ref "C2") (pin "2") (pintype "passive"))
      (node (ref "C20") (pin "1") (pinfunction "1_1") (pintype "passive"))
      (node (ref "C21") (pin "2") (pinfunction "2_2") (pintype "passive"))
      (node (ref "C25") (pin "2") (pinfunction "2_2") (pintype "passive"))
      (node (ref "C26") (pin "1") (pinfunction "1_1") (pintype "passive"))
      (node (ref "C3") (pin "1") (pinfunction "1_1") (pintype "passive"))
      (node (ref "C4") (pin "1") (pinfunction "1_1") (pintype "passive"))
      (node (ref "C5") (pin "1") (pintype "passive"))
      (node (ref "C6") (pin "1") (pintype "passive"))
      (node (ref "C7") (pin "1") (pinfunction "1_1") (pintype "passive"))
      (node (ref "C9") (pin "1") (pinfunction "1_1") (pintype "passive"))
      (node (ref "CB1") (pin "1") (pintype "passive"))
      (node (ref "EC1") (pin "2") (pinfunction "-_2") (pintype "passive"))
      (node (ref "EC2") (pin "2") (pinfunction "-_2") (pintype "passive"))
      (node (ref "EC3") (pin "2") (pinfunction "-_2") (pintype "passive"))
      (node (ref "JP1") (pin "2") (pinfunction "2_2") (pintype "passive"))
      (node (ref "JP2") (pin "1") (pinfunction "1_1") (pintype "passive"))
      (node (ref "JP3") (pin "1") (pinfunction "1_1") (pintype "passive"))
      (node (ref "JP4") (pin "4") (pinfunction "4_4") (pintype "passive"))
      (node (ref "NTC_IPM") (pin "2") (pinfunction "2_2") (pintype "passive"))
      (node (ref "PC1") (pin "3") (pinfunction "3_3") (pintype "passive"))
      (node (ref "PC3") (pin "3") (pinfunction "3_3") (pintype "passive"))
      (node (ref "R17") (pin "2") (pinfunction "2_2") (pintype "passive"))
      (node (ref "R21") (pin "1") (pinfunction "1_1") (pintype "passive"))
      (node (ref "R37") (pin "2") (pinfunction "2_2") (pintype "passive"))
      (node (ref "R47") (pin "1") (pinfunction "1_1") (pintype "passive"))
      (node (ref "R61") (pin "1") (pinfunction "1_1") (pintype "passive"))
      (node (ref "TVS1") (pin "1") (pinfunction "A_1") (pintype "passive"))
      (node (ref "U1") (pin "2") (pinfunction "GND_2") (pintype "passive"))
      (node (ref "U2") (pin "2") (pinfunction "GND_2") (pintype "passive"))
      (node (ref "U3") (pin "4") (pinfunction "COM_4") (pintype "passive"))
      (node (ref "U3") (pin "5") (pinfunction "COM_5") (pintype "passive"))
      (node (ref "U4") (pin "4") (pinfunction "COM_4") (pintype "passive"))
      (node (ref "U4") (pin "5") (pinfunction "COM_5") (pintype "passive"))
      (node (ref "U5") (pin "4") (pinfunction "COM_4") (pintype "passive"))
      (node (ref "U5") (pin "5") (pinfunction "COM_5") (pintype "passive"))
      (node (ref "U6") (pin "22") (pinfunction "GND_22") (pintype "passive"))
      (node (ref "U6") (pin "23") (pinfunction "GND_23") (pintype "passive"))
    )
    (net (code "43") (name "Net-(BD1-C-Pad3)") (class "Default")
      (node (ref "BD1") (pin "3") (pinfunction "C_3") (pintype "passive"))
      (node (ref "LF1") (pin "3") (pinfunction "3_3") (pintype "passive"))
    )
    (net (code "44") (name "Net-(C5-Pad2)") (class "Default")
      (node (ref "C5") (pin "2") (pintype "passive"))
      (node (ref "R11") (pin "1") (pinfunction "1_1") (pintype "passive"))
      (node (ref "R16") (pin "1") (pinfunction "1_1") (pintype "passive"))
      (node (ref "R21") (pin "2") (pinfunction "2_2") (pintype "passive"))
    )
    (net (code "45") (name "Net-(C24-Pad1)") (class "Default")
      (node (ref "C24") (pin "1") (pinfunction "1_1") (pintype "passive"))
      (node (ref "C25") (pin "1") (pinfunction "1_1") (pintype "passive"))
      (node (ref "PE1") (pin "1") (pintype "passive"))
    )
    (net (code "46") (name "Net-(EC3-+)") (class "Default")
      (node (ref "D1") (pin "2") (pinfunction "2_2") (pintype "passive"))
      (node (ref "EC3") (pin "1") (pinfunction "+_1") (pintype "passive"))
      (node (ref "U2") (pin "4") (pinfunction "DRAIN_4") (pintype "passive"))
    )
    (net (code "47") (name "Net-(JP1-Pad1)") (class "Default")
      (node (ref "JP1") (pin "1") (pinfunction "1_1") (pintype "passive"))
      (node (ref "R28") (pin "1") (pinfunction "1_1") (pintype "passive"))
      (node (ref "R34") (pin "1") (pinfunction "1_1") (pintype "passive"))
      (node (ref "R37") (pin "1") (pinfunction "1_1") (pintype "passive"))
    )
    (net (code "48") (name "Net-(JP3-Pad2)") (class "Default")
      (node (ref "JP3") (pin "2") (pinfunction "2_2") (pintype "passive"))
      (node (ref "R18") (pin "1") (pinfunction "1_1") (pintype "passive"))
    )
    (net (code "49") (name "Net-(JP3-Pad3)") (class "Default")
      (node (ref "JP3") (pin "3") (pinfunction "3_3") (pintype "passive"))
      (node (ref "R19") (pin "1") (pinfunction "1_1") (pintype "passive"))
    )
    (net (code "50") (name "Net-(JP3-Pad4)") (class "Default")
      (node (ref "JP3") (pin "4") (pinfunction "4_4") (pintype "passive"))
      (node (ref "R20") (pin "1") (pinfunction "1_1") (pintype "passive"))
    )
    (net (code "51") (name "Net-(L1-Pad2)") (class "Default")
      (node (ref "L1") (pin "2") (pinfunction "2_2") (pintype "passive"))
      (node (ref "U2") (pin "5") (pinfunction "IC_GND_5") (pintype "passive"))
      (node (ref "U2") (pin "6") (pinfunction "IC_GND_6") (pintype "passive"))
    )
    (net (code "52") (name "Net-(PC1-Pad1)") (class "Default")
      (node (ref "PC1") (pin "1") (pinfunction "1_1") (pintype "passive"))
      (node (ref "R33") (pin "2") (pinfunction "2_2") (pintype "passive"))
    )
    (net (code "53") (name "Net-(PC1-Pad4)") (class "Default")
      (node (ref "PC1") (pin "4") (pinfunction "4_4") (pintype "passive"))
      (node (ref "R25") (pin "1") (pinfunction "1_1") (pintype "passive"))
      (node (ref "R27") (pin "1") (pinfunction "1_1") (pintype "passive"))
    )
    (net (code "54") (name "Net-(PC2-A)") (class "Default")
      (node (ref "C8") (pin "1") (pinfunction "1_1") (pintype "passive"))
      (node (ref "PC2") (pin "1") (pinfunction "A_1") (pintype "passive"))
      (node (ref "R29") (pin "1") (pinfunction "1_1") (pintype "passive"))
      (node (ref "R36") (pin "2") (pinfunction "2_2") (pintype "passive"))
    )
    (net (code "55") (name "Net-(PC2-A{slash}K-Pad3)") (class "Default")
      (node (ref "PC2") (pin "3") (pinfunction "A/K_3") (pintype "passive"))
      (node (ref "T1") (pin "3") (pinfunction "3_3") (pintype "passive"))
    )
    (net (code "56") (name "Net-(PC2-A{slash}K-Pad4)") (class "Default")
      (node (ref "PC2") (pin "4") (pinfunction "A/K_4") (pintype "passive"))
      (node (ref "R31") (pin "1") (pinfunction "1_1") (pintype "passive"))
    )
    (net (code "57") (name "Net-(PC3-Pad1)") (class "Default")
      (node (ref "PC3") (pin "1") (pinfunction "1_1") (pintype "passive"))
      (node (ref "R44") (pin "2") (pinfunction "2_2") (pintype "passive"))
    )
    (net (code "58") (name "Net-(PC3-Pad4)") (class "Default")
      (node (ref "PC3") (pin "4") (pinfunction "4_4") (pintype "passive"))
      (node (ref "R39") (pin "1") (pinfunction "1_1") (pintype "passive"))
      (node (ref "R40") (pin "1") (pinfunction "1_1") (pintype "passive"))
    )
    (net (code "59") (name "Net-(R10-Pad1)") (class "Default")
      (node (ref "R10") (pin "1") (pinfunction "1_1") (pintype "passive"))
      (node (ref "R11") (pin "2") (pinfunction "2_2") (pintype "passive"))
    )
    (net (code "60") (name "Net-(R26-Pad1)") (class "Default")
      (node (ref "R26") (pin "1") (pinfunction "1_1") (pintype "passive"))
      (node (ref "R31") (pin "2") (pinfunction "2_2") (pintype "passive"))
    )
    (net (code "61") (name "Net-(R32-Pad2)") (class "Default")
      (node (ref "R32") (pin "2") (pinfunction "2_2") (pintype "passive"))
      (node (ref "R33") (pin "1") (pinfunction "1_1") (pintype "passive"))
    )
    (net (code "62") (name "Net-(R43-Pad2)") (class "Default")
      (node (ref "R43") (pin "2") (pinfunction "2_2") (pintype "passive"))
      (node (ref "R44") (pin "1") (pinfunction "1_1") (pintype "passive"))
    )
    (net (code "63") (name "Net-(RX1-Pad1)") (class "Default")
      (node (ref "RX1") (pin "1") (pinfunction "1_1") (pintype "passive"))
      (node (ref "RX2") (pin "2") (pinfunction "2_2") (pintype "passive"))
    )
    (net (code "64") (name "Net-(U1-Vin)") (class "Default")
      (node (ref "C1") (pin "2") (pinfunction "2_2") (pintype "passive"))
      (node (ref "C2") (pin "1") (pintype "passive"))
      (node (ref "R13") (pin "1") (pinfunction "1_1") (pintype "passive"))
      (node (ref "R15") (pin "1") (pinfunction "1_1") (pintype "passive"))
      (node (ref "U1") (pin "3") (pinfunction "Vin_3") (pintype "passive"))
    )
    (net (code "65") (name "Net-(U2-VOUT)") (class "Default")
      (node (ref "R12") (pin "2") (pinfunction "2_2") (pintype "passive"))
      (node (ref "U2") (pin "1") (pinfunction "VOUT_1") (pintype "passive"))
    )
    (net (code "66") (name "Net-(U3-HIN)") (class "Default")
      (node (ref "R41") (pin "2") (pinfunction "2_2") (pintype "passive"))
      (node (ref "U3") (pin "6") (pinfunction "HIN_6") (pintype "passive"))
    )
    (net (code "67") (name "Net-(U3-LIN)") (class "Default")
      (node (ref "R46") (pin "2") (pinfunction "2_2") (pintype "passive"))
      (node (ref "U3") (pin "7") (pinfunction "LIN_7") (pintype "passive"))
    )
    (net (code "68") (name "Net-(U3-N)") (class "Default")
      (node (ref "R53") (pin "1") (pinfunction "1_1") (pintype "passive"))
      (node (ref "R54") (pin "2") (pinfunction "2_2") (pintype "passive"))
      (node (ref "R67") (pin "1") (pinfunction "1_1") (pintype "passive"))
      (node (ref "U3") (pin "9") (pinfunction "N_9") (pintype "passive"))
    )
    (net (code "69") (name "Net-(U3-VB)") (class "Default")
      (node (ref "C12") (pin "1") (pinfunction "1_1") (pintype "passive"))
      (node (ref "U3") (pin "1") (pinfunction "VB_1") (pintype "passive"))
    )
    (net (code "70") (name "Net-(U3-VCCB)") (class "Default")
      (node (ref "R66") (pin "2") (pinfunction "2_2") (pintype "passive"))
      (node (ref "U3") (pin "2") (pinfunction "VCCB_2") (pintype "passive"))
    )
    (net (code "71") (name "Net-(U3-VTS)") (class "Default")
      (node (ref "D2") (pin "1") (pinfunction "1_1") (pintype "passive"))
      (node (ref "R67") (pin "2") (pinfunction "2_2") (pintype "passive"))
      (node (ref "U3") (pin "8") (pinfunction "VTS_8") (pintype "passive"))
    )
    (net (code "72") (name "Net-(U4-HIN)") (class "Default")
      (node (ref "R48") (pin "2") (pinfunction "2_2") (pintype "passive"))
      (node (ref "U4") (pin "6") (pinfunction "HIN_6") (pintype "passive"))
    )
    (net (code "73") (name "Net-(U4-LIN)") (class "Default")
      (node (ref "R49") (pin "2") (pinfunction "2_2") (pintype "passive"))
      (node (ref "U4") (pin "7") (pinfunction "LIN_7") (pintype "passive"))
    )
    (net (code "74") (name "Net-(U4-N)") (class "Default")
      (node (ref "R57") (pin "1") (pinfunction "1_1") (pintype "passive"))
      (node (ref "R58") (pin "2") (pinfunction "2_2") (pintype "passive"))
      (node (ref "R69") (pin "1") (pinfunction "1_1") (pintype "passive"))
      (node (ref "U4") (pin "9") (pinfunction "N_9") (pintype "passive"))
    )
    (net (code "75") (name "Net-(U4-VB)") (class "Default")
      (node (ref "C16") (pin "1") (pinfunction "1_1") (pintype "passive"))
      (node (ref "U4") (pin "1") (pinfunction "VB_1") (pintype "passive"))
    )
    (net (code "76") (name "Net-(U4-VCCB)") (class "Default")
      (node (ref "R68") (pin "2") (pinfunction "2_2") (pintype "passive"))
      (node (ref "U4") (pin "2") (pinfunction "VCCB_2") (pintype "passive"))
    )
    (net (code "77") (name "Net-(U4-VTS)") (class "Default")
      (node (ref "D3") (pin "1") (pinfunction "1_1") (pintype "passive"))
      (node (ref "R69") (pin "2") (pinfunction "2_2") (pintype "passive"))
      (node (ref "U4") (pin "8") (pinfunction "VTS_8") (pintype "passive"))
    )
    (net (code "78") (name "Net-(U5-HIN)") (class "Default")
      (node (ref "R50") (pin "2") (pinfunction "2_2") (pintype "passive"))
      (node (ref "U5") (pin "6") (pinfunction "HIN_6") (pintype "passive"))
    )
    (net (code "79") (name "Net-(U5-LIN)") (class "Default")
      (node (ref "R51") (pin "2") (pinfunction "2_2") (pintype "passive"))
      (node (ref "U5") (pin "7") (pinfunction "LIN_7") (pintype "passive"))
    )
    (net (code "80") (name "Net-(U5-VB)") (class "Default")
      (node (ref "C18") (pin "1") (pinfunction "1_1") (pintype "passive"))
      (node (ref "U5") (pin "1") (pinfunction "VB_1") (pintype "passive"))
    )
    (net (code "81") (name "Net-(U5-VCCB)") (class "Default")
      (node (ref "R70") (pin "2") (pinfunction "2_2") (pintype "passive"))
      (node (ref "U5") (pin "2") (pinfunction "VCCB_2") (pintype "passive"))
    )
    (net (code "82") (name "Net-(U5-VTS)") (class "Default")
      (node (ref "D4") (pin "1") (pinfunction "1_1") (pintype "passive"))
      (node (ref "R71") (pin "2") (pinfunction "2_2") (pintype "passive"))
      (node (ref "U5") (pin "8") (pinfunction "VTS_8") (pintype "passive"))
    )
    (net (code "83") (name "PGND") (class "Default")
      (node (ref "R45") (pin "1") (pinfunction "1_1") (pintype "passive"))
      (node (ref "R47") (pin "2") (pinfunction "2_2") (pintype "passive"))
      (node (ref "R54") (pin "1") (pinfunction "1_1") (pintype "passive"))
      (node (ref "R56") (pin "1") (pinfunction "1_1") (pintype "passive"))
      (node (ref "R58") (pin "1") (pinfunction "1_1") (pintype "passive"))
      (node (ref "R60") (pin "1") (pinfunction "1_1") (pintype "passive"))
      (node (ref "R61") (pin "2") (pinfunction "2_2") (pintype "passive"))
      (node (ref "R71") (pin "1") (pinfunction "1_1") (pintype "passive"))
      (node (ref "R72") (pin "1") (pinfunction "1_1") (pintype "passive"))
      (node (ref "U5") (pin "9") (pinfunction "N_9") (pintype "passive"))
    )
    (net (code "84") (name "Vbus") (class "Default")
      (node (ref "BD1") (pin "1") (pinfunction "K_1") (pintype "passive"))
      (node (ref "C24") (pin "2") (pinfunction "2_2") (pintype "passive"))
      (node (ref "CB1") (pin "2") (pintype "passive"))
      (node (ref "D1") (pin "1") (pinfunction "1_1") (pintype "passive"))
      (node (ref "EC1") (pin "1") (pinfunction "+_1") (pintype "passive"))
      (node (ref "R10") (pin "2") (pinfunction "2_2") (pintype "passive"))
      (node (ref "U3") (pin "12") (pinfunction "P_12") (pintype "passive"))
      (node (ref "U3") (pin "13") (pinfunction "P_13") (pintype "passive"))
      (node (ref "U3") (pin "15") (pinfunction "P_15") (pintype "passive"))
      (node (ref "U4") (pin "12") (pinfunction "P_12") (pintype "passive"))
      (node (ref "U4") (pin "13") (pinfunction "P_13") (pintype "passive"))
      (node (ref "U4") (pin "15") (pinfunction "P_15") (pintype "passive"))
      (node (ref "U5") (pin "12") (pinfunction "P_12") (pintype "passive"))
      (node (ref "U5") (pin "13") (pinfunction "P_13") (pintype "passive"))
      (node (ref "U5") (pin "15") (pinfunction "P_15") (pintype "passive"))
    )
    (net (code "85") (name "unconnected-(U2-FB-Pad8)") (class "Default")
      (node (ref "U2") (pin "8") (pinfunction "FB_8") (pintype "passive+no_connect"))
    )
    (net (code "86") (name "unconnected-(U2-NC-Pad3)") (class "Default")
      (node (ref "U2") (pin "3") (pinfunction "NC_3") (pintype "passive+no_connect"))
    )
  )
)
